# ds18b20_schematic.net
KiCad netlist of a schematic drawn in EAGLE
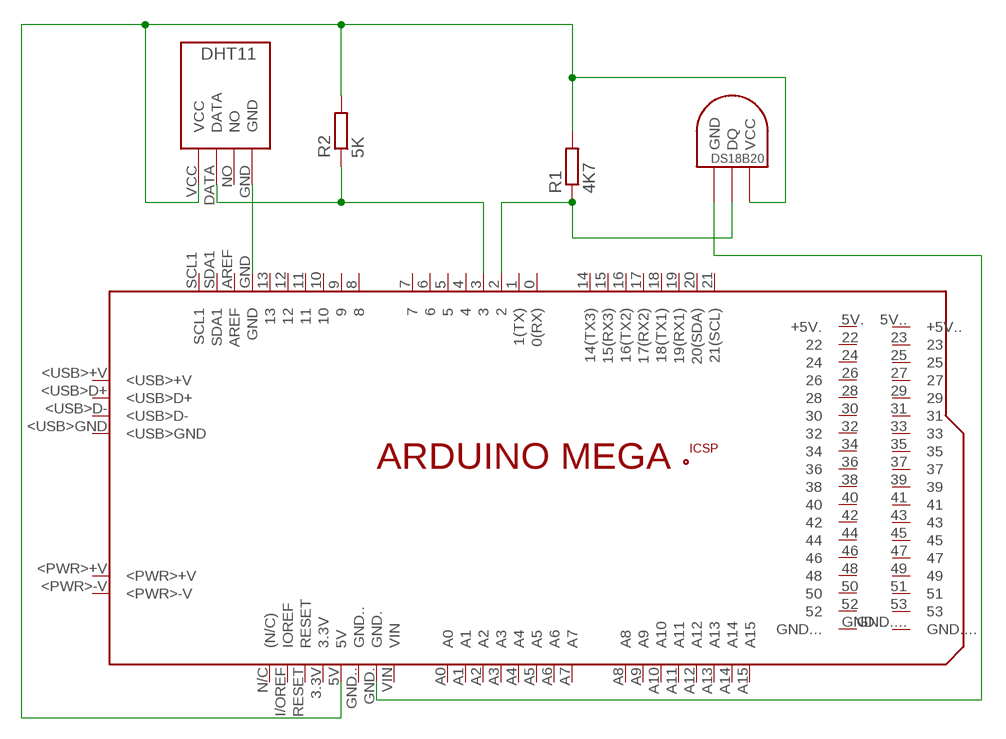
[diagram p0: schematic, sheet 1]

(export (version "E")
  (design (tool "Eeschema 10.0.6"))
  (components
    (comp (ref "PCB1")
      (value "ARDUINO_MEGA")
      (footprint "eagle-import:ARDUINO_MEGA")
      (libsource (lib "eagle-import") (part "ARDUINO_MEGA"))
    )
    (comp (ref "R1")
      (value "4K7")
      (footprint "eagle-import:0204_7")
      (libsource (lib "eagle-import") (part "R-EU_0204/7"))
    )
    (comp (ref "R2")
      (value "5K")
      (footprint "eagle-import:0204_7")
      (libsource (lib "eagle-import") (part "R-EU_0204/7"))
    )
    (comp (ref "U$1")
      (value "DS1820TO92")
      (footprint "eagle-import:DS1820")
      (libsource (lib "eagle-import") (part "DS1820TO92"))
    )
    (comp (ref "U$2")
      (value "DHT11-PION.")
      (footprint "eagle-import:DHT11-PION.")
      (libsource (lib "eagle-import") (part "DHT11-PION."))
    )
  )
  (nets
    (net (code "1") (name "Net-(PCB1-Pad2)") (class "Default")
      (node (ref "PCB1") (pin "2") (pinfunction "2_2") (pintype "bidirectional"))
      (node (ref "R1") (pin "1") (pinfunction "1_1") (pintype "passive"))
      (node (ref "U$1") (pin "DQ") (pinfunction "DQ_DQ") (pintype "bidirectional"))
    )
    (net (code "2") (name "Net-(PCB1-Pad3)") (class "Default")
      (node (ref "PCB1") (pin "3") (pinfunction "3_3") (pintype "bidirectional"))
      (node (ref "R2") (pin "1") (pinfunction "1_1") (pintype "passive"))
      (node (ref "U$2") (pin "DATA") (pinfunction "DATA_DATA") (pintype "bidirectional"))
    )
    (net (code "3") (name "Net-(PCB1-PadGND)") (class "Default")
      (node (ref "PCB1") (pin "GND") (pinfunction "GND_GND") (pintype "bidirectional"))
      (node (ref "U$2") (pin "GND") (pinfunction "GND_GND") (pintype "bidirectional"))
    )
    (net (code "4") (name "Net-(PCB1-PadGND.)") (class "Default")
      (node (ref "PCB1") (pin "GND.") (pinfunction "GND._GND.") (pintype "bidirectional"))
      (node (ref "U$1") (pin "GND") (pinfunction "GND_GND") (pintype "power_in"))
    )
    (net (code "5") (name "Net-(U$1-VCC)") (class "Default")
      (node (ref "PCB1") (pin "5V") (pinfunction "5V_5V") (pintype "bidirectional"))
      (node (ref "R1") (pin "2") (pinfunction "2_2") (pintype "passive"))
      (node (ref "R2") (pin "2") (pinfunction "2_2") (pintype "passive"))
      (node (ref "U$1") (pin "VDD") (pinfunction "VCC_VDD") (pintype "power_in"))
      (node (ref "U$2") (pin "VCC") (pinfunction "VCC_VCC") (pintype "bidirectional"))
    )
    (net (code "6") (name "unconnected-(PCB1-(N{slash}C)-PadN{slash}C)") (class "Default")
      (node (ref "PCB1") (pin "N/C") (pinfunction "(N/C)_N/C") (pintype "bidirectional"))
    )
    (net (code "7") (name "unconnected-(PCB1-+5V.-Pad5V.)") (class "Default")
      (node (ref "PCB1") (pin "5V.") (pinfunction "+5V._5V.") (pintype "bidirectional"))
    )
    (net (code "8") (name "unconnected-(PCB1-+5V..-Pad5V..)") (class "Default")
      (node (ref "PCB1") (pin "5V..") (pinfunction "+5V.._5V..") (pintype "bidirectional"))
    )
    (net (code "9") (name "unconnected-(PCB1-0(RX)-Pad0)") (class "Default")
      (node (ref "PCB1") (pin "0") (pinfunction "0(RX)_0") (pintype "bidirectional"))
    )
    (net (code "10") (name "unconnected-(PCB1-1(TX)-Pad1)") (class "Default")
      (node (ref "PCB1") (pin "1") (pinfunction "1(TX)_1") (pintype "bidirectional"))
    )
    (net (code "11") (name "unconnected-(PCB1-14(TX3)-Pad14)") (class "Default")
      (node (ref "PCB1") (pin "14") (pinfunction "14(TX3)_14") (pintype "bidirectional"))
    )
    (net (code "12") (name "unconnected-(PCB1-15(RX3)-Pad15)") (class "Default")
      (node (ref "PCB1") (pin "15") (pinfunction "15(RX3)_15") (pintype "bidirectional"))
    )
    (net (code "13") (name "unconnected-(PCB1-16(TX2)-Pad16)") (class "Default")
      (node (ref "PCB1") (pin "16") (pinfunction "16(TX2)_16") (pintype "bidirectional"))
    )
    (net (code "14") (name "unconnected-(PCB1-17(RX2)-Pad17)") (class "Default")
      (node (ref "PCB1") (pin "17") (pinfunction "17(RX2)_17") (pintype "bidirectional"))
    )
    (net (code "15") (name "unconnected-(PCB1-18(TX1)-Pad18)") (class "Default")
      (node (ref "PCB1") (pin "18") (pinfunction "18(TX1)_18") (pintype "bidirectional"))
    )
    (net (code "16") (name "unconnected-(PCB1-19(RX1)-Pad19)") (class "Default")
      (node (ref "PCB1") (pin "19") (pinfunction "19(RX1)_19") (pintype "bidirectional"))
    )
    (net (code "17") (name "unconnected-(PCB1-20(SDA)-Pad20)") (class "Default")
      (node (ref "PCB1") (pin "20") (pinfunction "20(SDA)_20") (pintype "bidirectional"))
    )
    (net (code "18") (name "unconnected-(PCB1-21(SCL)-Pad21)") (class "Default")
      (node (ref "PCB1") (pin "21") (pinfunction "21(SCL)_21") (pintype "bidirectional"))
    )
    (net (code "19") (name "unconnected-(PCB1-IOREF-PadI{slash}OREF)") (class "Default")
      (node (ref "PCB1") (pin "I/OREF") (pinfunction "IOREF_I/OREF") (pintype "bidirectional"))
    )
    (net (code "20") (name "unconnected-(PCB1-Pad+5V_)") (class "Default")
      (node (ref "PCB1") (pin "+5V_") (pinfunction "+5V__+5V_") (pintype "bidirectional"))
    )
    (net (code "21") (name "unconnected-(PCB1-Pad3.3V)") (class "Default")
      (node (ref "PCB1") (pin "3.3V") (pinfunction "3.3V_3.3V") (pintype "bidirectional"))
    )
    (net (code "22") (name "unconnected-(PCB1-Pad4)") (class "Default")
      (node (ref "PCB1") (pin "4") (pinfunction "4_4") (pintype "bidirectional"))
    )
    (net (code "23") (name "unconnected-(PCB1-Pad5)") (class "Default")
      (node (ref "PCB1") (pin "5") (pinfunction "5_5") (pintype "bidirectional"))
    )
    (net (code "24") (name "unconnected-(PCB1-Pad6)") (class "Default")
      (node (ref "PCB1") (pin "6") (pinfunction "6_6") (pintype "bidirectional"))
    )
    (net (code "25") (name "unconnected-(PCB1-Pad7)") (class "Default")
      (node (ref "PCB1") (pin "7") (pinfunction "7_7") (pintype "bidirectional"))
    )
    (net (code "26") (name "unconnected-(PCB1-Pad8)") (class "Default")
      (node (ref "PCB1") (pin "8") (pinfunction "8_8") (pintype "bidirectional"))
    )
    (net (code "27") (name "unconnected-(PCB1-Pad9)") (class "Default")
      (node (ref "PCB1") (pin "9") (pinfunction "9_9") (pintype "bidirectional"))
    )
    (net (code "28") (name "unconnected-(PCB1-Pad10)") (class "Default")
      (node (ref "PCB1") (pin "10") (pinfunction "10_10") (pintype "bidirectional"))
    )
    (net (code "29") (name "unconnected-(PCB1-Pad11)") (class "Default")
      (node (ref "PCB1") (pin "11") (pinfunction "11_11") (pintype "bidirectional"))
    )
    (net (code "30") (name "unconnected-(PCB1-Pad12)") (class "Default")
      (node (ref "PCB1") (pin "12") (pinfunction "12_12") (pintype "bidirectional"))
    )
    (net (code "31") (name "unconnected-(PCB1-Pad13)") (class "Default")
      (node (ref "PCB1") (pin "13") (pinfunction "13_13") (pintype "bidirectional"))
    )
    (net (code "32") (name "unconnected-(PCB1-Pad22)") (class "Default")
      (node (ref "PCB1") (pin "22") (pinfunction "22_22") (pintype "bidirectional"))
    )
    (net (code "33") (name "unconnected-(PCB1-Pad23)") (class "Default")
      (node (ref "PCB1") (pin "23") (pinfunction "23_23") (pintype "bidirectional"))
    )
    (net (code "34") (name "unconnected-(PCB1-Pad24)") (class "Default")
      (node (ref "PCB1") (pin "24") (pinfunction "24_24") (pintype "bidirectional"))
    )
    (net (code "35") (name "unconnected-(PCB1-Pad25)") (class "Default")
      (node (ref "PCB1") (pin "25") (pinfunction "25_25") (pintype "bidirectional"))
    )
    (net (code "36") (name "unconnected-(PCB1-Pad26)") (class "Default")
      (node (ref "PCB1") (pin "26") (pinfunction "26_26") (pintype "bidirectional"))
    )
    (net (code "37") (name "unconnected-(PCB1-Pad27)") (class "Default")
      (node (ref "PCB1") (pin "27") (pinfunction "27_27") (pintype "bidirectional"))
    )
    (net (code "38") (name "unconnected-(PCB1-Pad28)") (class "Default")
      (node (ref "PCB1") (pin "28") (pinfunction "28_28") (pintype "bidirectional"))
    )
    (net (code "39") (name "unconnected-(PCB1-Pad29)") (class "Default")
      (node (ref "PCB1") (pin "29") (pinfunction "29_29") (pintype "bidirectional"))
    )
    (net (code "40") (name "unconnected-(PCB1-Pad30)") (class "Default")
      (node (ref "PCB1") (pin "30") (pinfunction "30_30") (pintype "bidirectional"))
    )
    (net (code "41") (name "unconnected-(PCB1-Pad31)") (class "Default")
      (node (ref "PCB1") (pin "31") (pinfunction "31_31") (pintype "bidirectional"))
    )
    (net (code "42") (name "unconnected-(PCB1-Pad32)") (class "Default")
      (node (ref "PCB1") (pin "32") (pinfunction "32_32") (pintype "bidirectional"))
    )
    (net (code "43") (name "unconnected-(PCB1-Pad33)") (class "Default")
      (node (ref "PCB1") (pin "33") (pinfunction "33_33") (pintype "bidirectional"))
    )
    (net (code "44") (name "unconnected-(PCB1-Pad34)") (class "Default")
      (node (ref "PCB1") (pin "34") (pinfunction "34_34") (pintype "bidirectional"))
    )
    (net (code "45") (name "unconnected-(PCB1-Pad35)") (class "Default")
      (node (ref "PCB1") (pin "35") (pinfunction "35_35") (pintype "bidirectional"))
    )
    (net (code "46") (name "unconnected-(PCB1-Pad36)") (class "Default")
      (node (ref "PCB1") (pin "36") (pinfunction "36_36") (pintype "bidirectional"))
    )
    (net (code "47") (name "unconnected-(PCB1-Pad37)") (class "Default")
      (node (ref "PCB1") (pin "37") (pinfunction "37_37") (pintype "bidirectional"))
    )
    (net (code "48") (name "unconnected-(PCB1-Pad38)") (class "Default")
      (node (ref "PCB1") (pin "38") (pinfunction "38_38") (pintype "bidirectional"))
    )
    (net (code "49") (name "unconnected-(PCB1-Pad39)") (class "Default")
      (node (ref "PCB1") (pin "39") (pinfunction "39_39") (pintype "bidirectional"))
    )
    (net (code "50") (name "unconnected-(PCB1-Pad40)") (class "Default")
      (node (ref "PCB1") (pin "40") (pinfunction "40_40") (pintype "bidirectional"))
    )
    (net (code "51") (name "unconnected-(PCB1-Pad41)") (class "Default")
      (node (ref "PCB1") (pin "41") (pinfunction "41_41") (pintype "bidirectional"))
    )
    (net (code "52") (name "unconnected-(PCB1-Pad42)") (class "Default")
      (node (ref "PCB1") (pin "42") (pinfunction "42_42") (pintype "bidirectional"))
    )
    (net (code "53") (name "unconnected-(PCB1-Pad43)") (class "Default")
      (node (ref "PCB1") (pin "43") (pinfunction "43_43") (pintype "bidirectional"))
    )
    (net (code "54") (name "unconnected-(PCB1-Pad44)") (class "Default")
      (node (ref "PCB1") (pin "44") (pinfunction "44_44") (pintype "bidirectional"))
    )
    (net (code "55") (name "unconnected-(PCB1-Pad45)") (class "Default")
      (node (ref "PCB1") (pin "45") (pinfunction "45_45") (pintype "bidirectional"))
    )
    (net (code "56") (name "unconnected-(PCB1-Pad46)") (class "Default")
      (node (ref "PCB1") (pin "46") (pinfunction "46_46") (pintype "bidirectional"))
    )
    (net (code "57") (name "unconnected-(PCB1-Pad47)") (class "Default")
      (node (ref "PCB1") (pin "47") (pinfunction "47_47") (pintype "bidirectional"))
    )
    (net (code "58") (name "unconnected-(PCB1-Pad48)") (class "Default")
      (node (ref "PCB1") (pin "48") (pinfunction "48_48") (pintype "bidirectional"))
    )
    (net (code "59") (name "unconnected-(PCB1-Pad49)") (class "Default")
      (node (ref "PCB1") (pin "49") (pinfunction "49_49") (pintype "bidirectional"))
    )
    (net (code "60") (name "unconnected-(PCB1-Pad50)") (class "Default")
      (node (ref "PCB1") (pin "50") (pinfunction "50_50") (pintype "bidirectional"))
    )
    (net (code "61") (name "unconnected-(PCB1-Pad51)") (class "Default")
      (node (ref "PCB1") (pin "51") (pinfunction "51_51") (pintype "bidirectional"))
    )
    (net (code "62") (name "unconnected-(PCB1-Pad52)") (class "Default")
      (node (ref "PCB1") (pin "52") (pinfunction "52_52") (pintype "bidirectional"))
    )
    (net (code "63") (name "unconnected-(PCB1-Pad53)") (class "Default")
      (node (ref "PCB1") (pin "53") (pinfunction "53_53") (pintype "bidirectional"))
    )
    (net (code "64") (name "unconnected-(PCB1-Pad<PWR>+V)") (class "Default")
      (node (ref "PCB1") (pin "<PWR>+V") (pinfunction "<PWR>+V_<PWR>+V") (pintype "no_connect"))
    )
    (net (code "65") (name "unconnected-(PCB1-Pad<PWR>-V)") (class "Default")
      (node (ref "PCB1") (pin "<PWR>-V") (pinfunction "<PWR>-V_<PWR>-V") (pintype "no_connect"))
    )
    (net (code "66") (name "unconnected-(PCB1-Pad<USB>+V)") (class "Default")
      (node (ref "PCB1") (pin "<USB>+V") (pinfunction "<USB>+V_<USB>+V") (pintype "no_connect"))
    )
    (net (code "67") (name "unconnected-(PCB1-Pad<USB>D+)") (class "Default")
      (node (ref "PCB1") (pin "<USB>D+") (pinfunction "<USB>D+_<USB>D+") (pintype "no_connect"))
    )
    (net (code "68") (name "unconnected-(PCB1-Pad<USB>D-)") (class "Default")
      (node (ref "PCB1") (pin "<USB>D-") (pinfunction "<USB>D-_<USB>D-") (pintype "no_connect"))
    )
    (net (code "69") (name "unconnected-(PCB1-Pad<USB>GND)") (class "Default")
      (node (ref "PCB1") (pin "<USB>GND") (pinfunction "<USB>GND_<USB>GND") (pintype "no_connect"))
    )
    (net (code "70") (name "unconnected-(PCB1-PadA0)") (class "Default")
      (node (ref "PCB1") (pin "A0") (pinfunction "A0_A0") (pintype "bidirectional"))
    )
    (net (code "71") (name "unconnected-(PCB1-PadA1)") (class "Default")
      (node (ref "PCB1") (pin "A1") (pinfunction "A1_A1") (pintype "bidirectional"))
    )
    (net (code "72") (name "unconnected-(PCB1-PadA2)") (class "Default")
      (node (ref "PCB1") (pin "A2") (pinfunction "A2_A2") (pintype "bidirectional"))
    )
    (net (code "73") (name "unconnected-(PCB1-PadA3)") (class "Default")
      (node (ref "PCB1") (pin "A3") (pinfunction "A3_A3") (pintype "bidirectional"))
    )
    (net (code "74") (name "unconnected-(PCB1-PadA4)") (class "Default")
      (node (ref "PCB1") (pin "A4") (pinfunction "A4_A4") (pintype "bidirectional"))
    )
    (net (code "75") (name "unconnected-(PCB1-PadA5)") (class "Default")
      (node (ref "PCB1") (pin "A5") (pinfunction "A5_A5") (pintype "bidirectional"))
    )
    (net (code "76") (name "unconnected-(PCB1-PadA6)") (class "Default")
      (node (ref "PCB1") (pin "A6") (pinfunction "A6_A6") (pintype "bidirectional"))
    )
    (net (code "77") (name "unconnected-(PCB1-PadA7)") (class "Default")
      (node (ref "PCB1") (pin "A7") (pinfunction "A7_A7") (pintype "bidirectional"))
    )
    (net (code "78") (name "unconnected-(PCB1-PadA8)") (class "Default")
      (node (ref "PCB1") (pin "A8") (pinfunction "A8_A8") (pintype "bidirectional"))
    )
    (net (code "79") (name "unconnected-(PCB1-PadA9)") (class "Default")
      (node (ref "PCB1") (pin "A9") (pinfunction "A9_A9") (pintype "bidirectional"))
    )
    (net (code "80") (name "unconnected-(PCB1-PadA10)") (class "Default")
      (node (ref "PCB1") (pin "A10") (pinfunction "A10_A10") (pintype "bidirectional"))
    )
    (net (code "81") (name "unconnected-(PCB1-PadA11)") (class "Default")
      (node (ref "PCB1") (pin "A11") (pinfunction "A11_A11") (pintype "bidirectional"))
    )
    (net (code "82") (name "unconnected-(PCB1-PadA12)") (class "Default")
      (node (ref "PCB1") (pin "A12") (pinfunction "A12_A12") (pintype "bidirectional"))
    )
    (net (code "83") (name "unconnected-(PCB1-PadA13)") (class "Default")
      (node (ref "PCB1") (pin "A13") (pinfunction "A13_A13") (pintype "bidirectional"))
    )
    (net (code "84") (name "unconnected-(PCB1-PadA14)") (class "Default")
      (node (ref "PCB1") (pin "A14") (pinfunction "A14_A14") (pintype "bidirectional"))
    )
    (net (code "85") (name "unconnected-(PCB1-PadA15)") (class "Default")
      (node (ref "PCB1") (pin "A15") (pinfunction "A15_A15") (pintype "bidirectional"))
    )
    (net (code "86") (name "unconnected-(PCB1-PadAREF)") (class "Default")
      (node (ref "PCB1") (pin "AREF") (pinfunction "AREF_AREF") (pintype "bidirectional"))
    )
    (net (code "87") (name "unconnected-(PCB1-PadGND..)") (class "Default")
      (node (ref "PCB1") (pin "GND..") (pinfunction "GND.._GND..") (pintype "bidirectional"))
    )
    (net (code "88") (name "unconnected-(PCB1-PadGND...)") (class "Default")
      (node (ref "PCB1") (pin "GND...") (pinfunction "GND..._GND...") (pintype "bidirectional"))
    )
    (net (code "89") (name "unconnected-(PCB1-PadGND....)") (class "Default")
      (node (ref "PCB1") (pin "GND....") (pinfunction "GND...._GND....") (pintype "bidirectional"))
    )
    (net (code "90") (name "unconnected-(PCB1-PadGND__)") (class "Default")
      (node (ref "PCB1") (pin "GND__") (pinfunction "GND___GND__") (pintype "bidirectional"))
    )
    (net (code "91") (name "unconnected-(PCB1-PadMISO)") (class "Default")
      (node (ref "PCB1") (pin "MISO") (pinfunction "MISO_MISO") (pintype "bidirectional"))
    )
    (net (code "92") (name "unconnected-(PCB1-PadMOSI)") (class "Default")
      (node (ref "PCB1") (pin "MOSI") (pinfunction "MOSI_MOSI") (pintype "bidirectional"))
    )
    (net (code "93") (name "unconnected-(PCB1-PadRESET)") (class "Default")
      (node (ref "PCB1") (pin "RESET") (pinfunction "RESET_RESET") (pintype "bidirectional"))
    )
    (net (code "94") (name "unconnected-(PCB1-PadRESET.)") (class "Default")
      (node (ref "PCB1") (pin "RESET.") (pinfunction "RESET._RESET.") (pintype "bidirectional"))
    )
    (net (code "95") (name "unconnected-(PCB1-PadSCK)") (class "Default")
      (node (ref "PCB1") (pin "SCK") (pinfunction "SCK_SCK") (pintype "bidirectional"))
    )
    (net (code "96") (name "unconnected-(PCB1-PadSCL1)") (class "Default")
      (node (ref "PCB1") (pin "SCL1") (pinfunction "SCL1_SCL1") (pintype "bidirectional"))
    )
    (net (code "97") (name "unconnected-(PCB1-PadSDA1)") (class "Default")
      (node (ref "PCB1") (pin "SDA1") (pinfunction "SDA1_SDA1") (pintype "bidirectional"))
    )
    (net (code "98") (name "unconnected-(PCB1-PadVIN)") (class "Default")
      (node (ref "PCB1") (pin "VIN") (pinfunction "VIN_VIN") (pintype "bidirectional"))
    )
    (net (code "99") (name "unconnected-(U$2-PadNO)") (class "Default")
      (node (ref "U$2") (pin "NO") (pinfunction "NO_NO") (pintype "bidirectional"))
    )
  )
)
